# interface_dac_sma_feedback_2PS_ADC_detec.net
KiCad netlist of a schematic drawn in EAGLE
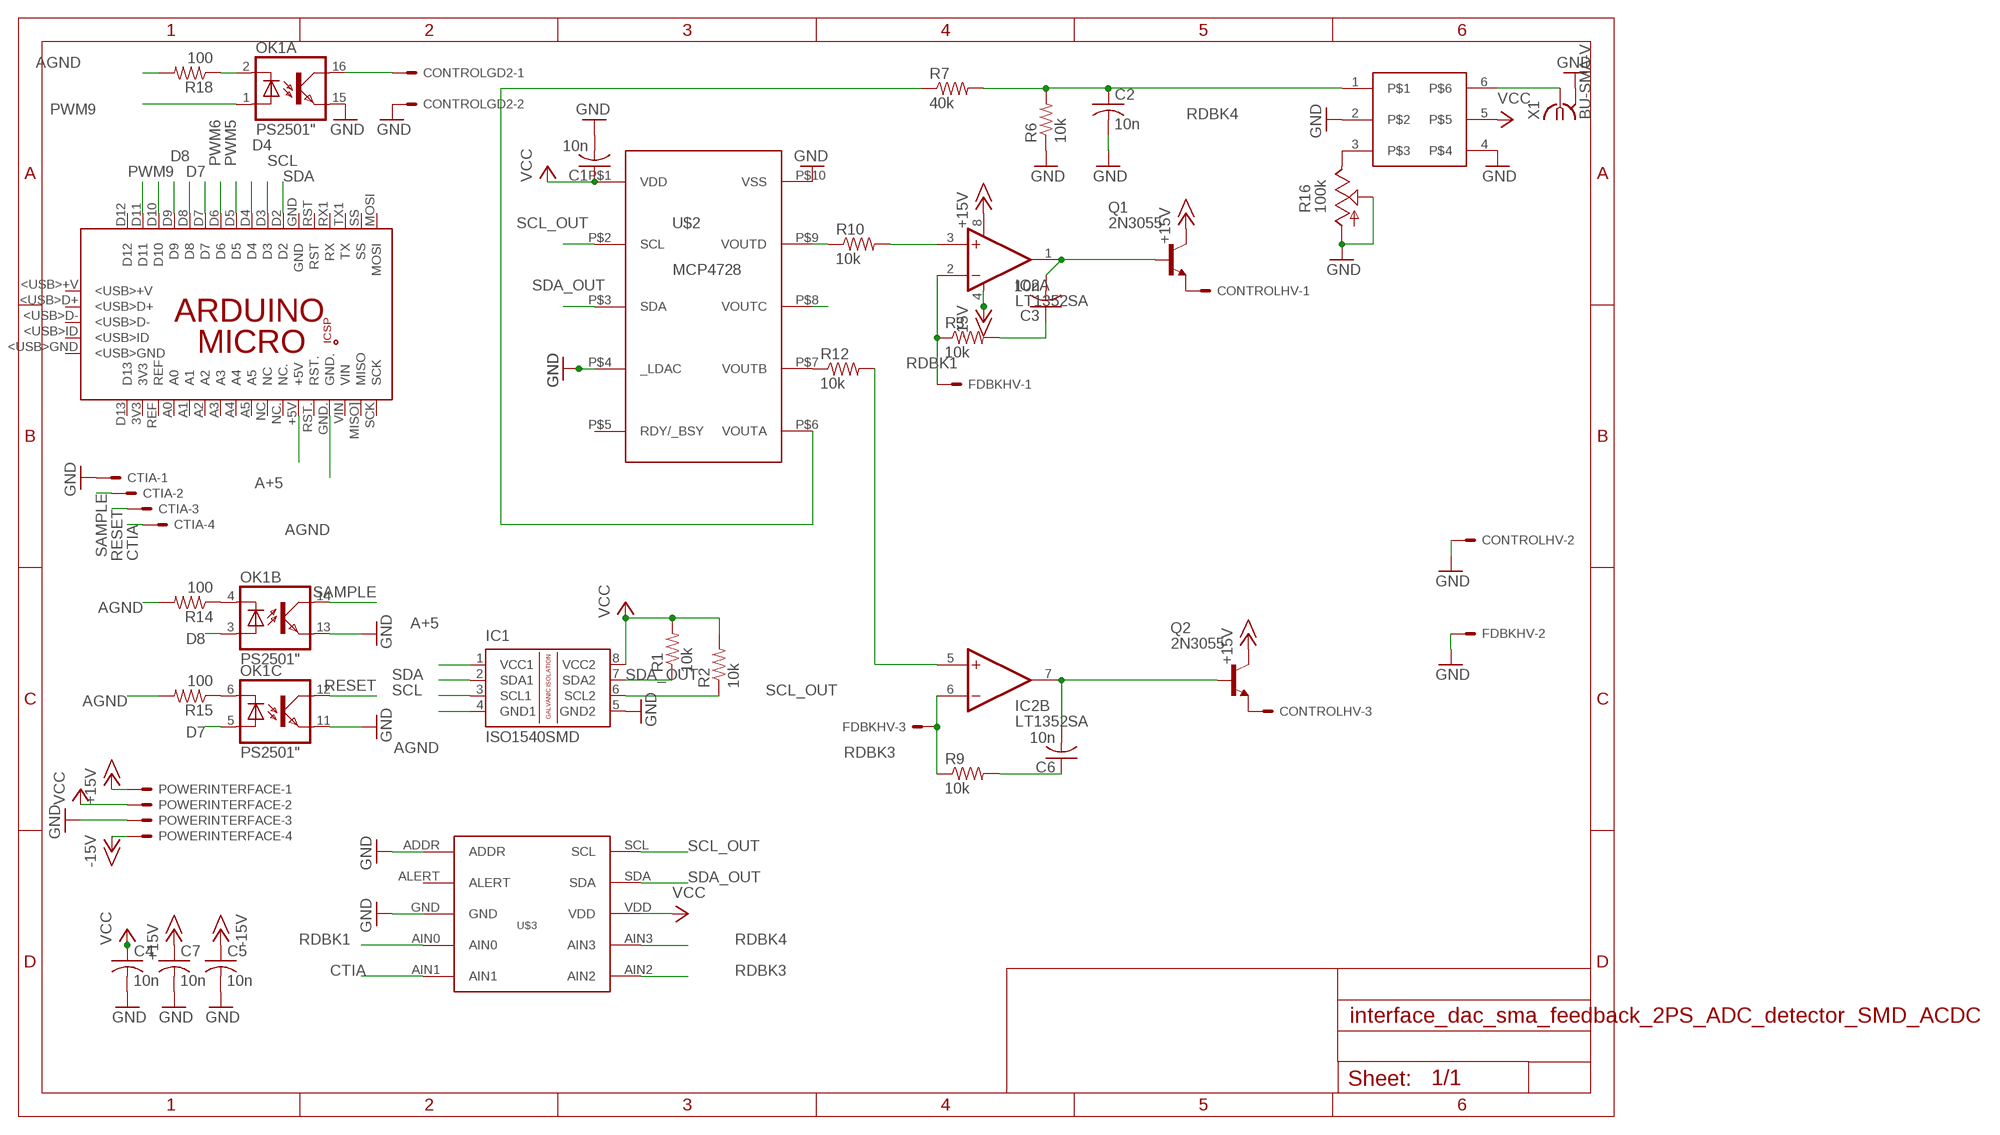
[diagram p0: schematic, sheet 1]

(export (version "E")
  (design (tool "Eeschema 10.0.6"))
  (components
    (comp (ref "C1")
      (value "10n")
      (footprint "eagle-import:C0805")
      (libsource (lib "eagle-import") (part "C-USC0805"))
    )
    (comp (ref "C2")
      (value "10n")
      (footprint "eagle-import:C0805")
      (libsource (lib "eagle-import") (part "resistor_C-USC0805"))
    )
    (comp (ref "C3")
      (value "10n")
      (footprint "eagle-import:C0805")
      (libsource (lib "eagle-import") (part "resistor_C-USC0805"))
    )
    (comp (ref "C4")
      (value "10n")
      (footprint "eagle-import:C0805")
      (libsource (lib "eagle-import") (part "resistor_C-USC0805"))
    )
    (comp (ref "C5")
      (value "10n")
      (footprint "eagle-import:C0805")
      (libsource (lib "eagle-import") (part "resistor_C-USC0805"))
    )
    (comp (ref "C6")
      (value "10n")
      (footprint "eagle-import:C0805")
      (libsource (lib "eagle-import") (part "resistor_C-USC0805"))
    )
    (comp (ref "C7")
      (value "10n")
      (footprint "eagle-import:C0805")
      (libsource (lib "eagle-import") (part "resistor_C-USC0805"))
    )
    (comp (ref "CONTROLGD2")
      (value "KK-156-2")
      (footprint "eagle-import:KK-156-2")
      (libsource (lib "eagle-import") (part "KK-156-2"))
    )
    (comp (ref "CONTROLHV")
      (value "KK-156-3")
      (footprint "eagle-import:KK-156-3")
      (libsource (lib "eagle-import") (part "KK-156-3"))
    )
    (comp (ref "CTIA")
      (value "KK-156-4")
      (footprint "eagle-import:KK-156-4")
      (libsource (lib "eagle-import") (part "KK-156-4"))
    )
    (comp (ref "FDBKHV")
      (value "KK-156-3")
      (footprint "eagle-import:KK-156-3")
      (libsource (lib "eagle-import") (part "KK-156-3"))
    )
    (comp (ref "IC1")
      (value "ISO1540SMD")
      (footprint "eagle-import:SOIC8")
      (libsource (lib "eagle-import") (part "ISO1540SMD"))
    )
    (comp (ref "IC2")
      (value "LT1352SA")
      (footprint "eagle-import:SO08")
      (libsource (lib "eagle-import") (part "LT1352SA"))
    )
    (comp (ref "OK1")
      (value "PS2501\"")
      (footprint "eagle-import:DIL16")
      (libsource (lib "eagle-import") (part "PS2501{dblquote}"))
    )
    (comp (ref "PCB1")
      (value "ARDUINO_MICRO")
      (footprint "eagle-import:ARDUINO_MICRO")
      (libsource (lib "eagle-import") (part "ARDUINO_MICRO"))
    )
    (comp (ref "POWERINTERFACE")
      (value "KK-156-4")
      (footprint "eagle-import:KK-156-4")
      (libsource (lib "eagle-import") (part "KK-156-4"))
    )
    (comp (ref "Q1")
      (value "2N3055")
      (footprint "eagle-import:TO3")
      (libsource (lib "eagle-import") (part "2N3055"))
    )
    (comp (ref "Q2")
      (value "2N3055")
      (footprint "eagle-import:TO3")
      (libsource (lib "eagle-import") (part "2N3055"))
    )
    (comp (ref "R1")
      (value "10k")
      (footprint "eagle-import:R0805")
      (libsource (lib "eagle-import") (part "resistor_R-US_R0805"))
    )
    (comp (ref "R2")
      (value "10k")
      (footprint "eagle-import:R0805")
      (libsource (lib "eagle-import") (part "resistor_R-US_R0805"))
    )
    (comp (ref "R3")
      (value "10k")
      (footprint "eagle-import:R0805")
      (libsource (lib "eagle-import") (part "resistor_R-US_R0805"))
    )
    (comp (ref "R6")
      (value "10k")
      (footprint "eagle-import:R0805")
      (libsource (lib "eagle-import") (part "resistor_R-US_R0805"))
    )
    (comp (ref "R7")
      (value "40k")
      (footprint "eagle-import:R0805")
      (libsource (lib "eagle-import") (part "resistor_R-US_R0805"))
    )
    (comp (ref "R9")
      (value "10k")
      (footprint "eagle-import:R0805")
      (libsource (lib "eagle-import") (part "resistor_R-US_R0805"))
    )
    (comp (ref "R10")
      (value "10k")
      (footprint "eagle-import:R0805")
      (libsource (lib "eagle-import") (part "resistor_R-US_R0805"))
    )
    (comp (ref "R12")
      (value "10k")
      (footprint "eagle-import:R0805")
      (libsource (lib "eagle-import") (part "resistor_R-US_R0805"))
    )
    (comp (ref "R14")
      (value "100")
      (footprint "eagle-import:R0805")
      (libsource (lib "eagle-import") (part "R-US_R0805"))
    )
    (comp (ref "R15")
      (value "100")
      (footprint "eagle-import:R0805")
      (libsource (lib "eagle-import") (part "R-US_R0805"))
    )
    (comp (ref "R16")
      (value "100k")
      (footprint "eagle-import:SP19L")
      (libsource (lib "eagle-import") (part "TRIM_US-B90P"))
    )
    (comp (ref "R18")
      (value "100")
      (footprint "eagle-import:R0805")
      (libsource (lib "eagle-import") (part "R-US_R0805"))
    )
    (comp (ref "U$1")
      (value "LTC6992SMD")
      (footprint "eagle-import:SOT23-6")
      (libsource (lib "eagle-import") (part "LTC6992SMD"))
    )
    (comp (ref "U$2")
      (value "MCP4728")
      (footprint "eagle-import:MSOP-10")
      (libsource (lib "eagle-import") (part "MCP4728"))
    )
    (comp (ref "U$3")
      (value "ADS1015")
      (footprint "eagle-import:VSOP-10")
      (libsource (lib "eagle-import") (part "ADS1015"))
    )
    (comp (ref "X1")
      (value "BU-SMA-V")
      (footprint "eagle-import:BU-SMA-V")
      (libsource (lib "eagle-import") (part "BU-SMA-V"))
    )
  )
  (nets
    (net (code "1") (name "+15V") (class "Default")
      (node (ref "C7") (pin "1") (pinfunction "1_1") (pintype "passive"))
      (node (ref "IC2") (pin "8") (pinfunction "V+_8") (pintype "power_in"))
      (node (ref "POWERINTERFACE") (pin "1") (pinfunction "S_1") (pintype "passive"))
      (node (ref "Q1") (pin "C") (pinfunction "C_C") (pintype "passive"))
      (node (ref "Q1") (pin "C/") (pinfunction "C_C/") (pintype "passive"))
      (node (ref "Q2") (pin "C") (pinfunction "C_C") (pintype "passive"))
      (node (ref "Q2") (pin "C/") (pinfunction "C_C/") (pintype "passive"))
    )
    (net (code "2") (name "-15V") (class "Default")
      (node (ref "C5") (pin "1") (pinfunction "1_1") (pintype "passive"))
      (node (ref "IC2") (pin "4") (pinfunction "V-_4") (pintype "power_in"))
      (node (ref "POWERINTERFACE") (pin "4") (pinfunction "S_4") (pintype "passive"))
    )
    (net (code "3") (name "/A+5") (class "Default")
      (node (ref "IC1") (pin "1") (pinfunction "VCC1_1") (pintype "input"))
      (node (ref "PCB1") (pin "+5V") (pinfunction "+5V_+5V") (pintype "bidirectional"))
    )
    (net (code "4") (name "/AGND") (class "Default")
      (node (ref "IC1") (pin "4") (pinfunction "GND1_4") (pintype "input"))
      (node (ref "PCB1") (pin "GND.") (pinfunction "GND._GND.") (pintype "bidirectional"))
      (node (ref "R14") (pin "2") (pinfunction "2_2") (pintype "passive"))
      (node (ref "R15") (pin "2") (pinfunction "2_2") (pintype "passive"))
      (node (ref "R18") (pin "2") (pinfunction "2_2") (pintype "passive"))
    )
    (net (code "5") (name "/CTIA") (class "Default")
      (node (ref "CTIA") (pin "4") (pinfunction "S_4") (pintype "passive"))
      (node (ref "U$3") (pin "AIN1") (pinfunction "AIN1_AIN1") (pintype "bidirectional"))
    )
    (net (code "6") (name "/D4") (class "Default")
      (node (ref "PCB1") (pin "D4") (pinfunction "D4_D4") (pintype "bidirectional"))
    )
    (net (code "7") (name "/D7") (class "Default")
      (node (ref "OK1") (pin "5") (pinfunction "A_5") (pintype "passive"))
      (node (ref "PCB1") (pin "D7") (pinfunction "D7_D7") (pintype "bidirectional"))
    )
    (net (code "8") (name "/D8") (class "Default")
      (node (ref "OK1") (pin "3") (pinfunction "A_3") (pintype "passive"))
      (node (ref "PCB1") (pin "D8") (pinfunction "D8_D8") (pintype "bidirectional"))
    )
    (net (code "9") (name "/PWM5") (class "Default")
      (node (ref "PCB1") (pin "D5") (pinfunction "D5_D5") (pintype "bidirectional"))
    )
    (net (code "10") (name "/PWM6") (class "Default")
      (node (ref "PCB1") (pin "D6") (pinfunction "D6_D6") (pintype "bidirectional"))
    )
    (net (code "11") (name "/PWM9") (class "Default")
      (node (ref "OK1") (pin "1") (pinfunction "A_1") (pintype "passive"))
      (node (ref "PCB1") (pin "D9") (pinfunction "D9_D9") (pintype "bidirectional"))
    )
    (net (code "12") (name "/RDBK1") (class "Default")
      (node (ref "FDBKHV") (pin "1") (pinfunction "S_1") (pintype "passive"))
      (node (ref "IC2") (pin "2") (pinfunction "-IN_2") (pintype "input"))
      (node (ref "R3") (pin "1") (pinfunction "1_1") (pintype "passive"))
      (node (ref "U$3") (pin "AIN0") (pinfunction "AIN0_AIN0") (pintype "bidirectional"))
    )
    (net (code "13") (name "/RDBK3") (class "Default")
      (node (ref "FDBKHV") (pin "3") (pinfunction "S_3") (pintype "passive"))
      (node (ref "IC2") (pin "6") (pinfunction "-IN_6") (pintype "input"))
      (node (ref "R9") (pin "1") (pinfunction "1_1") (pintype "passive"))
      (node (ref "U$3") (pin "AIN2") (pinfunction "AIN2_AIN2") (pintype "bidirectional"))
    )
    (net (code "14") (name "/RDBK4") (class "Default")
      (node (ref "C2") (pin "1") (pinfunction "1_1") (pintype "passive"))
      (node (ref "R6") (pin "2") (pinfunction "2_2") (pintype "passive"))
      (node (ref "R7") (pin "2") (pinfunction "2_2") (pintype "passive"))
      (node (ref "U$1") (pin "1") (pinfunction "P$1_1") (pintype "bidirectional"))
      (node (ref "U$3") (pin "AIN3") (pinfunction "AIN3_AIN3") (pintype "bidirectional"))
    )
    (net (code "15") (name "/RESET") (class "Default")
      (node (ref "CTIA") (pin "3") (pinfunction "S_3") (pintype "passive"))
      (node (ref "OK1") (pin "12") (pinfunction "COL_12") (pintype "passive"))
    )
    (net (code "16") (name "/SAMPLE") (class "Default")
      (node (ref "CTIA") (pin "2") (pinfunction "S_2") (pintype "passive"))
      (node (ref "OK1") (pin "14") (pinfunction "COL_14") (pintype "passive"))
    )
    (net (code "17") (name "/SCL") (class "Default")
      (node (ref "IC1") (pin "3") (pinfunction "SCL1_3") (pintype "input"))
      (node (ref "PCB1") (pin "D3") (pinfunction "D3_D3") (pintype "bidirectional"))
    )
    (net (code "18") (name "/SCL_OUT") (class "Default")
      (node (ref "IC1") (pin "6") (pinfunction "SCL2_6") (pintype "input"))
      (node (ref "R2") (pin "1") (pinfunction "1_1") (pintype "passive"))
      (node (ref "U$2") (pin "P$2") (pinfunction "SCL_P$2") (pintype "bidirectional"))
      (node (ref "U$3") (pin "SCL") (pinfunction "SCL_SCL") (pintype "bidirectional"))
    )
    (net (code "19") (name "/SDA") (class "Default")
      (node (ref "IC1") (pin "2") (pinfunction "SDA1_2") (pintype "input"))
      (node (ref "PCB1") (pin "D2") (pinfunction "D2_D2") (pintype "bidirectional"))
    )
    (net (code "20") (name "/SDA_OUT") (class "Default")
      (node (ref "IC1") (pin "7") (pinfunction "SDA2_7") (pintype "input"))
      (node (ref "R1") (pin "1") (pinfunction "1_1") (pintype "passive"))
      (node (ref "U$2") (pin "P$3") (pinfunction "SDA_P$3") (pintype "bidirectional"))
      (node (ref "U$3") (pin "SDA") (pinfunction "SDA_SDA") (pintype "bidirectional"))
    )
    (net (code "21") (name "GND") (class "Default")
      (node (ref "C1") (pin "2") (pinfunction "2_2") (pintype "passive"))
      (node (ref "C2") (pin "2") (pinfunction "2_2") (pintype "passive"))
      (node (ref "C4") (pin "2") (pinfunction "2_2") (pintype "passive"))
      (node (ref "C5") (pin "2") (pinfunction "2_2") (pintype "passive"))
      (node (ref "C7") (pin "2") (pinfunction "2_2") (pintype "passive"))
      (node (ref "CONTROLGD2") (pin "2") (pinfunction "S_2") (pintype "passive"))
      (node (ref "CONTROLHV") (pin "2") (pinfunction "S_2") (pintype "passive"))
      (node (ref "CTIA") (pin "1") (pinfunction "S_1") (pintype "passive"))
      (node (ref "FDBKHV") (pin "2") (pinfunction "S_2") (pintype "passive"))
      (node (ref "IC1") (pin "5") (pinfunction "GND2_5") (pintype "input"))
      (node (ref "OK1") (pin "11") (pinfunction "EMI_11") (pintype "passive"))
      (node (ref "OK1") (pin "13") (pinfunction "EMI_13") (pintype "passive"))
      (node (ref "OK1") (pin "15") (pinfunction "EMI_15") (pintype "passive"))
      (node (ref "POWERINTERFACE") (pin "3") (pinfunction "S_3") (pintype "passive"))
      (node (ref "R16") (pin "A") (pinfunction "A_A") (pintype "passive"))
      (node (ref "R16") (pin "S") (pinfunction "S_S") (pintype "passive"))
      (node (ref "R6") (pin "1") (pinfunction "1_1") (pintype "passive"))
      (node (ref "U$1") (pin "2") (pinfunction "P$2_2") (pintype "bidirectional"))
      (node (ref "U$1") (pin "4") (pinfunction "P$4_4") (pintype "bidirectional"))
      (node (ref "U$2") (pin "P$10") (pinfunction "VSS_P$10") (pintype "bidirectional"))
      (node (ref "U$2") (pin "P$4") (pinfunction "_LDAC_P$4") (pintype "bidirectional"))
      (node (ref "U$3") (pin "ADDR") (pinfunction "ADDR_ADDR") (pintype "bidirectional"))
      (node (ref "U$3") (pin "GND") (pinfunction "GND_GND") (pintype "bidirectional"))
      (node (ref "X1") (pin "2") (pinfunction "2_2") (pintype "passive"))
      (node (ref "X1") (pin "3") (pinfunction "2_3") (pintype "passive"))
      (node (ref "X1") (pin "4") (pinfunction "2_4") (pintype "passive"))
      (node (ref "X1") (pin "5") (pinfunction "2_5") (pintype "passive"))
    )
    (net (code "22") (name "Net-(C3-Pad1)") (class "Default")
      (node (ref "C3") (pin "1") (pinfunction "1_1") (pintype "passive"))
      (node (ref "R3") (pin "2") (pinfunction "2_2") (pintype "passive"))
    )
    (net (code "23") (name "Net-(C6-Pad1)") (class "Default")
      (node (ref "C6") (pin "1") (pinfunction "1_1") (pintype "passive"))
      (node (ref "R9") (pin "2") (pinfunction "2_2") (pintype "passive"))
    )
    (net (code "24") (name "Net-(CONTROLGD2A-S)") (class "Default")
      (node (ref "CONTROLGD2") (pin "1") (pinfunction "S_1") (pintype "passive"))
      (node (ref "OK1") (pin "16") (pinfunction "COL_16") (pintype "passive"))
    )
    (net (code "25") (name "Net-(CONTROLHVA-S)") (class "Default")
      (node (ref "CONTROLHV") (pin "1") (pinfunction "S_1") (pintype "passive"))
      (node (ref "Q1") (pin "E") (pinfunction "E_E") (pintype "passive"))
    )
    (net (code "26") (name "Net-(CONTROLHVC-S)") (class "Default")
      (node (ref "CONTROLHV") (pin "3") (pinfunction "S_3") (pintype "passive"))
      (node (ref "Q2") (pin "E") (pinfunction "E_E") (pintype "passive"))
    )
    (net (code "27") (name "Net-(IC2A-+IN)") (class "Default")
      (node (ref "IC2") (pin "3") (pinfunction "+IN_3") (pintype "input"))
      (node (ref "R10") (pin "2") (pinfunction "2_2") (pintype "passive"))
    )
    (net (code "28") (name "Net-(IC2A-OUT)") (class "Default")
      (node (ref "C3") (pin "2") (pinfunction "2_2") (pintype "passive"))
      (node (ref "IC2") (pin "1") (pinfunction "OUT_1") (pintype "output"))
      (node (ref "Q1") (pin "B") (pinfunction "B_B") (pintype "passive"))
    )
    (net (code "29") (name "Net-(IC2B-+IN)") (class "Default")
      (node (ref "IC2") (pin "5") (pinfunction "+IN_5") (pintype "input"))
      (node (ref "R12") (pin "2") (pinfunction "2_2") (pintype "passive"))
    )
    (net (code "30") (name "Net-(IC2B-OUT)") (class "Default")
      (node (ref "C6") (pin "2") (pinfunction "2_2") (pintype "passive"))
      (node (ref "IC2") (pin "7") (pinfunction "OUT_7") (pintype "output"))
      (node (ref "Q2") (pin "B") (pinfunction "B_B") (pintype "passive"))
    )
    (net (code "31") (name "Net-(OK1A-C)") (class "Default")
      (node (ref "OK1") (pin "2") (pinfunction "C_2") (pintype "passive"))
      (node (ref "R18") (pin "1") (pinfunction "1_1") (pintype "passive"))
    )
    (net (code "32") (name "Net-(OK1B-C)") (class "Default")
      (node (ref "OK1") (pin "4") (pinfunction "C_4") (pintype "passive"))
      (node (ref "R14") (pin "1") (pinfunction "1_1") (pintype "passive"))
    )
    (net (code "33") (name "Net-(OK1C-C)") (class "Default")
      (node (ref "OK1") (pin "6") (pinfunction "C_6") (pintype "passive"))
      (node (ref "R15") (pin "1") (pinfunction "1_1") (pintype "passive"))
    )
    (net (code "34") (name "Net-(U$1-P$3)") (class "Default")
      (node (ref "R16") (pin "E") (pinfunction "E_E") (pintype "passive"))
      (node (ref "U$1") (pin "3") (pinfunction "P$3_3") (pintype "bidirectional"))
    )
    (net (code "35") (name "Net-(U$1-P$6)") (class "Default")
      (node (ref "U$1") (pin "6") (pinfunction "P$6_6") (pintype "bidirectional"))
      (node (ref "X1") (pin "1") (pinfunction "1_1") (pintype "passive"))
    )
    (net (code "36") (name "Net-(U$2-VOUTA)") (class "Default")
      (node (ref "R7") (pin "1") (pinfunction "1_1") (pintype "passive"))
      (node (ref "U$2") (pin "P$6") (pinfunction "VOUTA_P$6") (pintype "bidirectional"))
    )
    (net (code "37") (name "Net-(U$2-VOUTB)") (class "Default")
      (node (ref "R12") (pin "1") (pinfunction "1_1") (pintype "passive"))
      (node (ref "U$2") (pin "P$7") (pinfunction "VOUTB_P$7") (pintype "bidirectional"))
    )
    (net (code "38") (name "Net-(U$2-VOUTD)") (class "Default")
      (node (ref "R10") (pin "1") (pinfunction "1_1") (pintype "passive"))
      (node (ref "U$2") (pin "P$9") (pinfunction "VOUTD_P$9") (pintype "bidirectional"))
    )
    (net (code "39") (name "VCC") (class "Default")
      (node (ref "C1") (pin "1") (pinfunction "1_1") (pintype "passive"))
      (node (ref "C4") (pin "1") (pinfunction "1_1") (pintype "passive"))
      (node (ref "IC1") (pin "8") (pinfunction "VCC2_8") (pintype "input"))
      (node (ref "POWERINTERFACE") (pin "2") (pinfunction "S_2") (pintype "passive"))
      (node (ref "R1") (pin "2") (pinfunction "2_2") (pintype "passive"))
      (node (ref "R2") (pin "2") (pinfunction "2_2") (pintype "passive"))
      (node (ref "U$1") (pin "5") (pinfunction "P$5_5") (pintype "bidirectional"))
      (node (ref "U$2") (pin "P$1") (pinfunction "VDD_P$1") (pintype "bidirectional"))
      (node (ref "U$3") (pin "VDD") (pinfunction "VDD_VDD") (pintype "bidirectional"))
    )
    (net (code "40") (name "unconnected-(PCB1-MISO-PadMISO])") (class "Default")
      (node (ref "PCB1") (pin "MISO]") (pinfunction "MISO_MISO]") (pintype "bidirectional"))
    )
    (net (code "41") (name "unconnected-(PCB1-Pad3V3)") (class "Default")
      (node (ref "PCB1") (pin "3V3") (pinfunction "3V3_3V3") (pintype "bidirectional"))
    )
    (net (code "42") (name "unconnected-(PCB1-Pad5V)") (class "Default")
      (node (ref "PCB1") (pin "5V") (pinfunction "5V_5V") (pintype "bidirectional"))
    )
    (net (code "43") (name "unconnected-(PCB1-Pad<USB>+V)") (class "Default")
      (node (ref "PCB1") (pin "<USB>+V") (pinfunction "<USB>+V_<USB>+V") (pintype "bidirectional"))
    )
    (net (code "44") (name "unconnected-(PCB1-Pad<USB>D+)") (class "Default")
      (node (ref "PCB1") (pin "<USB>D+") (pinfunction "<USB>D+_<USB>D+") (pintype "bidirectional"))
    )
    (net (code "45") (name "unconnected-(PCB1-Pad<USB>D-)") (class "Default")
      (node (ref "PCB1") (pin "<USB>D-") (pinfunction "<USB>D-_<USB>D-") (pintype "bidirectional"))
    )
    (net (code "46") (name "unconnected-(PCB1-Pad<USB>GND)") (class "Default")
      (node (ref "PCB1") (pin "<USB>GND") (pinfunction "<USB>GND_<USB>GND") (pintype "bidirectional"))
    )
    (net (code "47") (name "unconnected-(PCB1-Pad<USB>ID)") (class "Default")
      (node (ref "PCB1") (pin "<USB>ID") (pinfunction "<USB>ID_<USB>ID") (pintype "bidirectional"))
    )
    (net (code "48") (name "unconnected-(PCB1-PadA0)") (class "Default")
      (node (ref "PCB1") (pin "A0") (pinfunction "A0_A0") (pintype "bidirectional"))
    )
    (net (code "49") (name "unconnected-(PCB1-PadA1)") (class "Default")
      (node (ref "PCB1") (pin "A1") (pinfunction "A1_A1") (pintype "bidirectional"))
    )
    (net (code "50") (name "unconnected-(PCB1-PadA2)") (class "Default")
      (node (ref "PCB1") (pin "A2") (pinfunction "A2_A2") (pintype "bidirectional"))
    )
    (net (code "51") (name "unconnected-(PCB1-PadA3)") (class "Default")
      (node (ref "PCB1") (pin "A3") (pinfunction "A3_A3") (pintype "bidirectional"))
    )
    (net (code "52") (name "unconnected-(PCB1-PadA4)") (class "Default")
      (node (ref "PCB1") (pin "A4") (pinfunction "A4_A4") (pintype "bidirectional"))
    )
    (net (code "53") (name "unconnected-(PCB1-PadA5)") (class "Default")
      (node (ref "PCB1") (pin "A5") (pinfunction "A5_A5") (pintype "bidirectional"))
    )
    (net (code "54") (name "unconnected-(PCB1-PadD10)") (class "Default")
      (node (ref "PCB1") (pin "D10") (pinfunction "D10_D10") (pintype "bidirectional"))
    )
    (net (code "55") (name "unconnected-(PCB1-PadD11)") (class "Default")
      (node (ref "PCB1") (pin "D11") (pinfunction "D11_D11") (pintype "bidirectional"))
    )
    (net (code "56") (name "unconnected-(PCB1-PadD12)") (class "Default")
      (node (ref "PCB1") (pin "D12") (pinfunction "D12_D12") (pintype "bidirectional"))
    )
    (net (code "57") (name "unconnected-(PCB1-PadD13)") (class "Default")
      (node (ref "PCB1") (pin "D13") (pinfunction "D13_D13") (pintype "bidirectional"))
    )
    (net (code "58") (name "unconnected-(PCB1-PadGND)") (class "Default")
      (node (ref "PCB1") (pin "GND") (pinfunction "GND_GND") (pintype "bidirectional"))
    )
    (net (code "59") (name "unconnected-(PCB1-PadGND_)") (class "Default")
      (node (ref "PCB1") (pin "GND_") (pinfunction "GND__GND_") (pintype "bidirectional"))
    )
    (net (code "60") (name "unconnected-(PCB1-PadMISO.)") (class "Default")
      (node (ref "PCB1") (pin "MISO.") (pinfunction "MISO._MISO.") (pintype "bidirectional"))
    )
    (net (code "61") (name "unconnected-(PCB1-PadMOSI)") (class "Default")
      (node (ref "PCB1") (pin "MOSI") (pinfunction "MOSI_MOSI") (pintype "bidirectional"))
    )
    (net (code "62") (name "unconnected-(PCB1-PadMOSI.)") (class "Default")
      (node (ref "PCB1") (pin "MOSI.") (pinfunction "MOSI._MOSI.") (pintype "bidirectional"))
    )
    (net (code "63") (name "unconnected-(PCB1-PadNC)") (class "Default")
      (node (ref "PCB1") (pin "NC") (pinfunction "NC_NC") (pintype "bidirectional"))
    )
    (net (code "64") (name "unconnected-(PCB1-PadNC.)") (class "Default")
      (node (ref "PCB1") (pin "NC.") (pinfunction "NC._NC.") (pintype "bidirectional"))
    )
    (net (code "65") (name "unconnected-(PCB1-PadREF)") (class "Default")
      (node (ref "PCB1") (pin "REF") (pinfunction "REF_REF") (pintype "bidirectional"))
    )
    (net (code "66") (name "unconnected-(PCB1-PadRESET..)") (class "Default")
      (node (ref "PCB1") (pin "RESET..") (pinfunction "RESET.._RESET..") (pintype "bidirectional"))
    )
    (net (code "67") (name "unconnected-(PCB1-PadRST)") (class "Default")
      (node (ref "PCB1") (pin "RST") (pinfunction "RST_RST") (pintype "bidirectional"))
    )
    (net (code "68") (name "unconnected-(PCB1-PadRST.)") (class "Default")
      (node (ref "PCB1") (pin "RST.") (pinfunction "RST._RST.") (pintype "bidirectional"))
    )
    (net (code "69") (name "unconnected-(PCB1-PadSCK)") (class "Default")
      (node (ref "PCB1") (pin "SCK") (pinfunction "SCK_SCK") (pintype "bidirectional"))
    )
    (net (code "70") (name "unconnected-(PCB1-PadSCK.)") (class "Default")
      (node (ref "PCB1") (pin "SCK.") (pinfunction "SCK._SCK.") (pintype "bidirectional"))
    )
    (net (code "71") (name "unconnected-(PCB1-PadSS)") (class "Default")
      (node (ref "PCB1") (pin "SS") (pinfunction "SS_SS") (pintype "bidirectional"))
    )
    (net (code "72") (name "unconnected-(PCB1-PadVIN)") (class "Default")
      (node (ref "PCB1") (pin "VIN") (pinfunction "VIN_VIN") (pintype "bidirectional"))
    )
    (net (code "73") (name "unconnected-(PCB1-RX-PadRX1)") (class "Default")
      (node (ref "PCB1") (pin "RX1") (pinfunction "RX_RX1") (pintype "bidirectional"))
    )
    (net (code "74") (name "unconnected-(PCB1-TX-PadTX1)") (class "Default")
      (node (ref "PCB1") (pin "TX1") (pinfunction "TX_TX1") (pintype "bidirectional"))
    )
    (net (code "75") (name "unconnected-(U$2-RDY{slash}_BSY-PadP$5)") (class "Default")
      (node (ref "U$2") (pin "P$5") (pinfunction "RDY/_BSY_P$5") (pintype "bidirectional"))
    )
    (net (code "76") (name "unconnected-(U$2-VOUTC-PadP$8)") (class "Default")
      (node (ref "U$2") (pin "P$8") (pinfunction "VOUTC_P$8") (pintype "bidirectional"))
    )
    (net (code "77") (name "unconnected-(U$3-PadALERT)") (class "Default")
      (node (ref "U$3") (pin "ALERT") (pinfunction "ALERT_ALERT") (pintype "bidirectional"))
    )
  )
)
